# Sheet1.net
KiCad netlist of a schematic drawn in Altium Designer
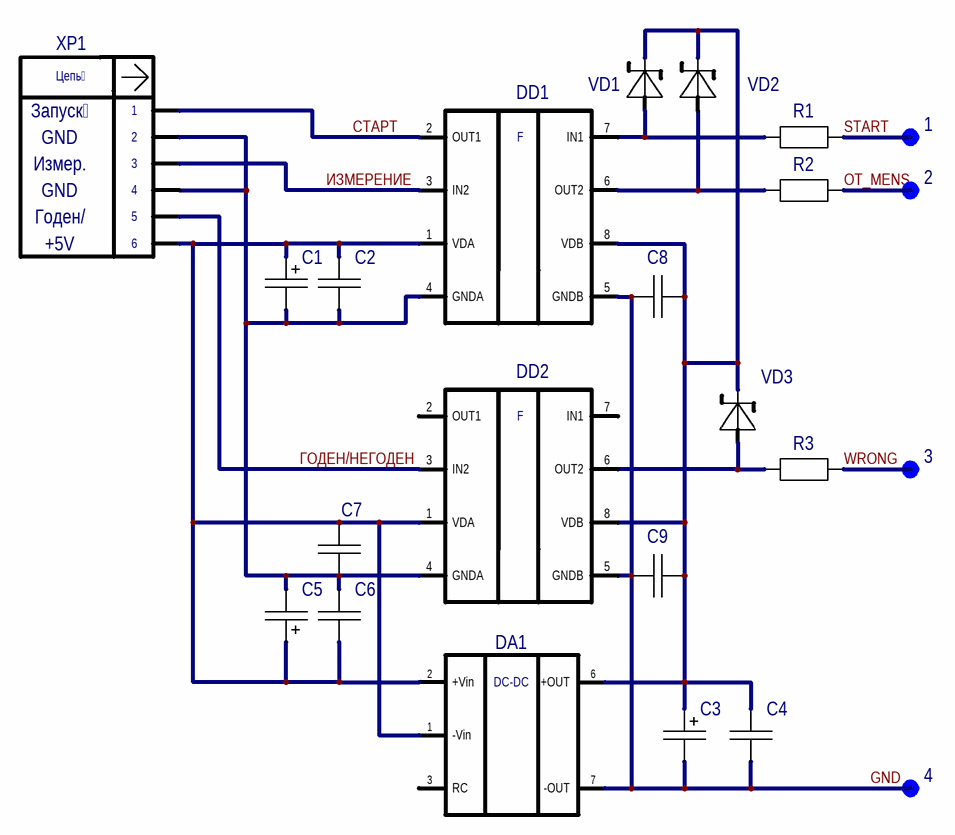
[diagram p0: Sheet1.SCHDOC]

(export (version "E")
  (design (tool "Eeschema 10.0.6"))
  (components
    (comp (ref "1")
      (value "ТОЧКА ПАЙКИ 1")
      (footprint "LEPESTOK7_750_224")
      (libsource (lib "*") (part "ТОЧКА ПАЙКИ 1"))
    )
    (comp (ref "2")
      (value "ТОЧКА ПАЙКИ 1")
      (footprint "LEPESTOK7_750_224")
      (libsource (lib "*") (part "ТОЧКА ПАЙКИ 1"))
    )
    (comp (ref "3")
      (value "ТОЧКА ПАЙКИ 1")
      (footprint "LEPESTOK7_750_224")
      (libsource (lib "*") (part "ТОЧКА ПАЙКИ 1"))
    )
    (comp (ref "4")
      (value "ТОЧКА ПАЙКИ 1")
      (footprint "LEPESTOK7_750_224")
      (libsource (lib "*") (part "ТОЧКА ПАЙКИ 1"))
    )
    (comp (ref "C1")
      (value "TAJB476K10RNJ")
      (footprint "TANT_B")
      (libsource (lib "*") (part "TAJB476K10RNJ"))
    )
    (comp (ref "C2")
      (value "0805-2F3-0,1 MKФ")
      (footprint "0805")
      (libsource (lib "*") (part "0805-2F3-0,1 MKФ"))
    )
    (comp (ref "C3")
      (value "TAJB476K10RNJ")
      (footprint "TANT_B")
      (libsource (lib "*") (part "TAJB476K10RNJ"))
    )
    (comp (ref "C4")
      (value "0805-2F3-0,1 MKФ")
      (footprint "0805")
      (libsource (lib "*") (part "0805-2F3-0,1 MKФ"))
    )
    (comp (ref "C5")
      (value "TAJB476K10RNJ")
      (footprint "TANT_B")
      (libsource (lib "*") (part "TAJB476K10RNJ"))
    )
    (comp (ref "C6")
      (value "0805-2F3-0,1 MKФ")
      (footprint "0805")
      (libsource (lib "*") (part "0805-2F3-0,1 MKФ"))
    )
    (comp (ref "C7")
      (value "0805-2F3-0,1 MKФ")
      (footprint "0805")
      (libsource (lib "*") (part "0805-2F3-0,1 MKФ"))
    )
    (comp (ref "C8")
      (value "0805-2F3-0,1 MKФ")
      (footprint "0805")
      (libsource (lib "*") (part "0805-2F3-0,1 MKФ"))
    )
    (comp (ref "C9")
      (value "0805-2F3-0,1 MKФ")
      (footprint "0805")
      (libsource (lib "*") (part "0805-2F3-0,1 MKФ"))
    )
    (comp (ref "DA1")
      (value "ПРЕОБРАЗОВАТЕЛЬ SPB 03E-05")
      (footprint "SPB 03")
      (libsource (lib "*") (part "ПРЕОБРАЗОВАТЕЛЬ SPB 03E-05"))
    )
    (comp (ref "DD1") (value "ADUM1201AR") (footprint "R-8") (libsource (lib "*") (part "ADUM1201AR")))
    (comp (ref "DD2") (value "ADUM1201AR") (footprint "R-8") (libsource (lib "*") (part "ADUM1201AR")))
    (comp (ref "R1")
      (value "1206-100 ОМ+-5%")
      (footprint "1206")
      (libsource (lib "*") (part "1206-100 ОМ+-5%"))
    )
    (comp (ref "R2")
      (value "1206-100 ОМ+-5%")
      (footprint "1206")
      (libsource (lib "*") (part "1206-100 ОМ+-5%"))
    )
    (comp (ref "R3")
      (value "1206-100 ОМ+-5%")
      (footprint "1206")
      (libsource (lib "*") (part "1206-100 ОМ+-5%"))
    )
    (comp (ref "VD1") (value "BAT 42WS") (footprint "SOD-323") (libsource (lib "*") (part "BAT 42WS")))
    (comp (ref "VD2") (value "BAT 42WS") (footprint "SOD-323") (libsource (lib "*") (part "BAT 42WS")))
    (comp (ref "VD3") (value "BAT 42WS") (footprint "SOD-323") (libsource (lib "") (part "BAT 42WS_1")))
    (comp (ref "XP1")
      (value "AMP II 280372-2")
      (footprint "AMPMODU-0-280372-2_1X6")
      (libsource (lib "*") (part "AMP II 280372-2"))
    )
  )
  (nets
    (net (code "1") (name "/GND") (class "Default")
      (node (ref "4") (pin "1") (pinfunction "1_1") (pintype "passive"))
      (node (ref "C3") (pin "2") (pintype "passive"))
      (node (ref "C4") (pin "1") (pintype "passive"))
      (node (ref "C8") (pin "2") (pintype "passive"))
      (node (ref "C9") (pin "2") (pintype "passive"))
      (node (ref "DA1") (pin "7") (pinfunction "-OUT_7") (pintype "passive"))
      (node (ref "DD1") (pin "5") (pinfunction "GNDB_5") (pintype "passive"))
      (node (ref "DD2") (pin "5") (pinfunction "GNDB_5") (pintype "passive"))
    )
    (net (code "4") (name "/WRONG") (class "Default")
      (node (ref "3") (pin "1") (pinfunction "1_1") (pintype "passive"))
      (node (ref "R3") (pin "2") (pinfunction "1_2") (pintype "passive"))
    )
    (net (code "5") (name "/ГОДЕН{slash}НЕГОДЕН") (class "Default")
      (node (ref "DD2") (pin "3") (pinfunction "IN2_3") (pintype "passive"))
      (node (ref "XP1") (pin "5") (pinfunction "5_5") (pintype "passive"))
    )
    (net (code "8") (name "Net-(1-Pad1)") (class "Default")
      (node (ref "1") (pin "1") (pinfunction "1_1") (pintype "passive"))
      (node (ref "R1") (pin "2") (pinfunction "1_2") (pintype "passive"))
    )
    (net (code "9") (name "Net-(2-Pad1)") (class "Default")
      (node (ref "2") (pin "1") (pinfunction "1_1") (pintype "passive"))
      (node (ref "R2") (pin "2") (pinfunction "1_2") (pintype "passive"))
    )
    (net (code "10") (name "Net-(DA1-+OUT)") (class "Default")
      (node (ref "C3") (pin "1") (pintype "passive"))
      (node (ref "C4") (pin "2") (pintype "passive"))
      (node (ref "C8") (pin "1") (pintype "passive"))
      (node (ref "C9") (pin "1") (pintype "passive"))
      (node (ref "DA1") (pin "6") (pinfunction "+OUT_6") (pintype "passive"))
      (node (ref "DD1") (pin "8") (pinfunction "VDB_8") (pintype "passive"))
      (node (ref "DD2") (pin "8") (pinfunction "VDB_8") (pintype "passive"))
      (node (ref "VD1") (pin "2") (pinfunction "-_2") (pintype "passive"))
      (node (ref "VD2") (pin "2") (pinfunction "-_2") (pintype "passive"))
      (node (ref "VD3") (pin "2") (pinfunction "-_2") (pintype "passive"))
    )
    (net (code "11") (name "Net-(DA1-+Vin)") (class "Default")
      (node (ref "C1") (pin "1") (pintype "passive"))
      (node (ref "C2") (pin "2") (pintype "passive"))
      (node (ref "C5") (pin "1") (pintype "passive"))
      (node (ref "C6") (pin "2") (pintype "passive"))
      (node (ref "C7") (pin "2") (pintype "passive"))
      (node (ref "DA1") (pin "1") (pinfunction "-Vin_1") (pintype "passive"))
      (node (ref "DA1") (pin "2") (pinfunction "+Vin_2") (pintype "passive"))
      (node (ref "DD1") (pin "1") (pinfunction "VDA_1") (pintype "passive"))
      (node (ref "DD2") (pin "1") (pinfunction "VDA_1") (pintype "passive"))
      (node (ref "XP1") (pin "6") (pinfunction "6_6") (pintype "passive"))
    )
    (net (code "12") (name "Net-(DD1-GNDA)") (class "Default")
      (node (ref "C1") (pin "2") (pintype "passive"))
      (node (ref "C2") (pin "1") (pintype "passive"))
      (node (ref "C5") (pin "2") (pintype "passive"))
      (node (ref "C6") (pin "1") (pintype "passive"))
      (node (ref "C7") (pin "1") (pintype "passive"))
      (node (ref "DD1") (pin "4") (pinfunction "GNDA_4") (pintype "passive"))
      (node (ref "DD2") (pin "4") (pinfunction "GNDA_4") (pintype "passive"))
      (node (ref "XP1") (pin "2") (pinfunction "2_2") (pintype "passive"))
      (node (ref "XP1") (pin "4") (pinfunction "4_4") (pintype "passive"))
    )
    (net (code "13") (name "Net-(DD1-IN1)") (class "Default")
      (node (ref "DD1") (pin "7") (pinfunction "IN1_7") (pintype "passive"))
      (node (ref "R1") (pin "1") (pinfunction "1_1") (pintype "passive"))
      (node (ref "VD1") (pin "1") (pinfunction "+_1") (pintype "passive"))
    )
    (net (code "14") (name "Net-(DD1-IN2)") (class "Default")
      (node (ref "DD1") (pin "3") (pinfunction "IN2_3") (pintype "passive"))
      (node (ref "XP1") (pin "3") (pinfunction "3_3") (pintype "passive"))
    )
    (net (code "15") (name "Net-(DD1-OUT1)") (class "Default")
      (node (ref "DD1") (pin "2") (pinfunction "OUT1_2") (pintype "passive"))
      (node (ref "XP1") (pin "1") (pinfunction "1_1") (pintype "passive"))
    )
    (net (code "16") (name "Net-(DD1-OUT2)") (class "Default")
      (node (ref "DD1") (pin "6") (pinfunction "OUT2_6") (pintype "passive"))
      (node (ref "R2") (pin "1") (pinfunction "1_1") (pintype "passive"))
      (node (ref "VD2") (pin "1") (pinfunction "+_1") (pintype "passive"))
    )
    (net (code "17") (name "Net-(DD2-OUT2)") (class "Default")
      (node (ref "DD2") (pin "6") (pinfunction "OUT2_6") (pintype "passive"))
      (node (ref "R3") (pin "1") (pinfunction "1_1") (pintype "passive"))
      (node (ref "VD3") (pin "1") (pinfunction "+_1") (pintype "passive"))
    )
    (net (code "18") (name "unconnected-(DA1-Pad5)") (class "Default")
      (node (ref "DA1") (pin "5") (pintype "passive"))
    )
    (net (code "19") (name "unconnected-(DA1-Pad8)") (class "Default")
      (node (ref "DA1") (pin "8") (pintype "passive"))
    )
    (net (code "20") (name "unconnected-(DA1-RC-Pad3)") (class "Default")
      (node (ref "DA1") (pin "3") (pinfunction "RC_3") (pintype "passive"))
    )
    (net (code "21") (name "unconnected-(DD2-IN1-Pad7)") (class "Default")
      (node (ref "DD2") (pin "7") (pinfunction "IN1_7") (pintype "passive"))
    )
    (net (code "22") (name "unconnected-(DD2-OUT1-Pad2)") (class "Default")
      (node (ref "DD2") (pin "2") (pinfunction "OUT1_2") (pintype "passive"))
    )
  )
)
